# MCU.net
KiCad netlist of a schematic drawn in Altium Designer
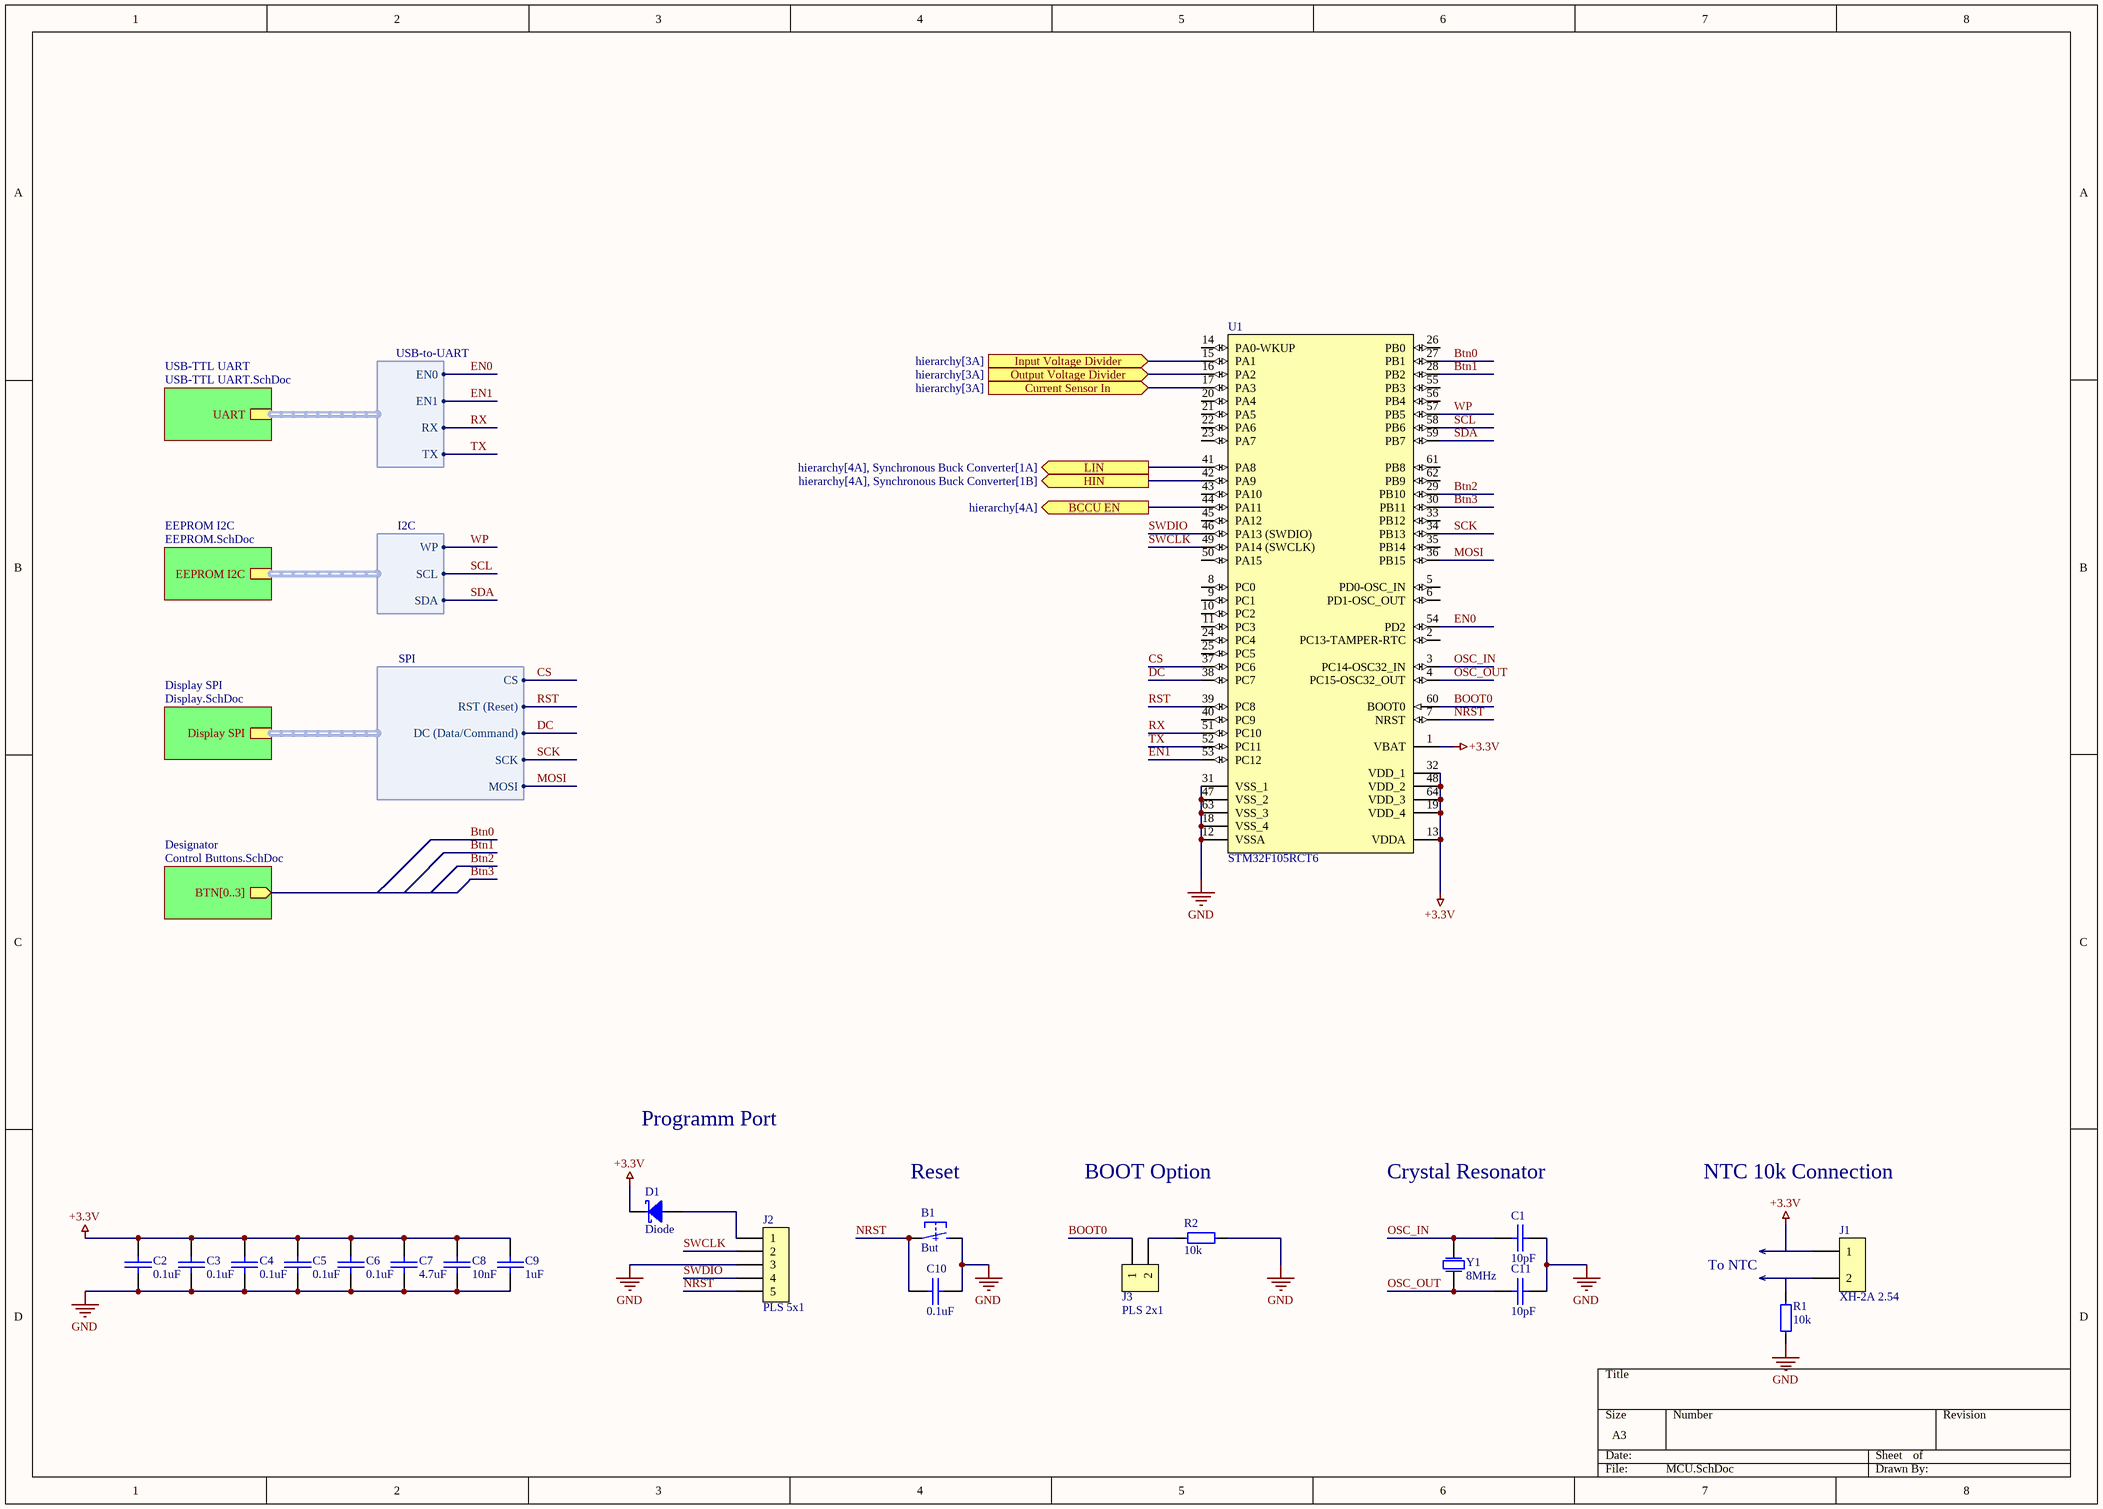
[diagram p0: MCU.SchDoc]

(export (version "E")
  (design (tool "Eeschema 10.0.6"))
  (components
    (comp (ref "B1")
      (value "But")
      (footprint "BUTTON 6x3.5")
      (description "Button 2 Conn SMD")
      (fields
        (field (name "PART NUMBER") "L-KLS7-TS3608-5.0-180")
        (field (name "MANUFACTURER") "KLS electronic co ltd")
      )
      (libsource (lib "BRT_Components") (part "Button 2 Conn"))
    )
    (comp (ref "C1")
      (value "10pF")
      (footprint "0805 Capicator")
      (description "10pF NP0 50V 5% 0805")
      (fields
        (field (name "MANUFACTURER") "Murata Manufacturing")
        (field (name "PART NUMBER") "GRM2165C1H100JZ01D")
      )
      (libsource (lib "BRT_Components") (part "Cap 10pF (0805)"))
    )
    (comp (ref "C2")
      (value "0.1uF")
      (footprint "0603 Capicator")
      (description "0.1uF X7R 16V 10% 0603")
      (fields
        (field (name "MANUFACTURER") "Murata Manufacturing")
        (field (name "PART NUMBER") "GRM188R71C104KA01D")
      )
      (libsource (lib "BRT_Components") (part "Cap 0.1uF (0603)"))
    )
    (comp (ref "C3")
      (value "0.1uF")
      (footprint "0603 Capicator")
      (description "0.1uF X7R 16V 10% 0603")
      (fields
        (field (name "MANUFACTURER") "Murata Manufacturing")
        (field (name "PART NUMBER") "GRM188R71C104KA01D")
      )
      (libsource (lib "BRT_Components") (part "Cap 0.1uF (0603)"))
    )
    (comp (ref "C4")
      (value "0.1uF")
      (footprint "0603 Capicator")
      (description "0.1uF X7R 16V 10% 0603")
      (fields
        (field (name "MANUFACTURER") "Murata Manufacturing")
        (field (name "PART NUMBER") "GRM188R71C104KA01D")
      )
      (libsource (lib "BRT_Components") (part "Cap 0.1uF (0603)"))
    )
    (comp (ref "C5")
      (value "0.1uF")
      (footprint "0603 Capicator")
      (description "0.1uF X7R 16V 10% 0603")
      (fields
        (field (name "MANUFACTURER") "Murata Manufacturing")
        (field (name "PART NUMBER") "GRM188R71C104KA01D")
      )
      (libsource (lib "BRT_Components") (part "Cap 0.1uF (0603)"))
    )
    (comp (ref "C6")
      (value "0.1uF")
      (footprint "0603 Capicator")
      (description "0.1uF X7R 16V 10% 0603")
      (fields
        (field (name "MANUFACTURER") "Murata Manufacturing")
        (field (name "PART NUMBER") "GRM188R71C104KA01D")
      )
      (libsource (lib "BRT_Components") (part "Cap 0.1uF (0603)"))
    )
    (comp (ref "C7")
      (value "4.7uF")
      (footprint "0603 Capicator")
      (description "4.7uF X5R 25V 10% 0603")
      (fields
        (field (name "MANUFACTURER") "Murata Manufacturing")
        (field (name "PART NUMBER") "GRM188R61E475KE11D")
      )
      (libsource (lib "BRT_Components") (part "Cap 4.7uF (0603)"))
    )
    (comp (ref "C8")
      (value "10nF")
      (footprint "0603 Capicator")
      (description "X7R 10nF 100V 10% 0603")
      (fields
        (field (name "MANUFACTURER") "Murata Manufacturing")
        (field (name "PART NUMBER") "GRM188R72A103KA01D")
      )
      (libsource (lib "BRT_Components") (part "Cap 10nF (0603)"))
    )
    (comp (ref "C9")
      (value "1uF")
      (footprint "0603 Capicator")
      (description "1uF X5R 25V 10% 0603")
      (fields
        (field (name "MANUFACTURER") "Murata Manufacturing")
        (field (name "PART NUMBER") "GRM188R61E105KAADD")
      )
      (libsource (lib "BRT_Components") (part "Cap 1uF (0603)"))
    )
    (comp (ref "C10")
      (value "0.1uF")
      (footprint "0805 Capicator")
      (description "0.1uF X7R 25V 10% 0805")
      (fields
        (field (name "MANUFACTURER") "Murata Manufacturing")
        (field (name "PART NUMBER") "GRM21BR71E104KA01L")
      )
      (libsource (lib "BRT_Components") (part "Cap 0.1uF (0805)"))
    )
    (comp (ref "C11")
      (value "10pF")
      (footprint "0805 Capicator")
      (description "10pF NP0 50V 5% 0805")
      (fields
        (field (name "MANUFACTURER") "Murata Manufacturing")
        (field (name "PART NUMBER") "GRM2165C1H100JZ01D")
      )
      (libsource (lib "BRT_Components") (part "Cap 10pF (0805)"))
    )
    (comp (ref "D1")
      (value "Diode")
      (footprint "sod-123")
      (description "0.5 A, Low Forward Voltage less than 385 mV, 400 mW Power Dissipation Package")
      (fields (field (name "PART NUMBER") "MBR0520L") (field (name "MANUFACTURER") "ON Semiconductor"))
      (libsource (lib "BRT_Components") (part "Diode Schottky (SOD-123)"))
    )
    (comp (ref "J1")
      (value "XH-2A 2.54")
      (footprint "CONN 1X2 (XH 2.54)")
      (description "Connector on the board straight 2pin 2.54mm")
      (libsource (lib "Altium_Library") (part "Connector XH-2A 2.54"))
    )
    (comp (ref "J2")
      (value "PLS 5x1")
      (footprint "PLS 5x1")
      (description "Header, 5-Pin")
      (libsource (lib "BRT_Components") (part "Conn 5 (PLS)"))
    )
    (comp (ref "J3")
      (value "PLS 2x1")
      (footprint "PLS 2X1")
      (libsource (lib "BRT_Components") (part "Conn 2 (PLS)"))
    )
    (comp (ref "R1")
      (value "10k")
      (footprint "0805 Resistor")
      (description "0.125W 0805 10k, 1%")
      (fields (field (name "PART NUMBER") "RC0805FR-0710KL") (field (name "MANUFACTURER") "Taiwan"))
      (libsource (lib "BRT_Components") (part "Res 10k (0805)"))
    )
    (comp (ref "R2")
      (value "10k")
      (footprint "0805 Resistor")
      (description "0.125W 0805 10k, 1%")
      (fields (field (name "PART NUMBER") "RC0805FR-0710KL") (field (name "MANUFACTURER") "Taiwan"))
      (libsource (lib "BRT_Components") (part "Res 10k (0805)"))
    )
    (comp (ref "U1")
      (value "STM32F105RCT6")
      (footprint "LQFP64")
      (description "MCU ARM 256KB FLASH MEM 64-LQFP")
      (fields (field (name "MANUFACTURER") "STMicroelectronics"))
      (libsource (lib "BRT_Components") (part "STM32F105RCT6"))
    )
    (comp (ref "Y1")
      (value "8MHz")
      (footprint "R38")
      (description "Crystal. HC-49S (US)")
      (fields (field (name "MANUFACTURER") "China") (field (name "PART NUMBER") "8.000MHzHC-49US"))
      (libsource (lib "BRT_Components") (part "Crystal 8MHz"))
    )
  )
  (nets
    (net (code "4") (name "+3.3V") (class "Default")
      (node (ref "C2") (pin "2") (pinfunction "2_2") (pintype "passive"))
      (node (ref "C3") (pin "2") (pinfunction "2_2") (pintype "passive"))
      (node (ref "C4") (pin "2") (pinfunction "2_2") (pintype "passive"))
      (node (ref "C5") (pin "2") (pinfunction "2_2") (pintype "passive"))
      (node (ref "C6") (pin "2") (pinfunction "2_2") (pintype "passive"))
      (node (ref "C7") (pin "2") (pinfunction "2_2") (pintype "passive"))
      (node (ref "C8") (pin "2") (pinfunction "2_2") (pintype "passive"))
      (node (ref "C9") (pin "2") (pinfunction "2_2") (pintype "passive"))
      (node (ref "D1") (pin "2") (pinfunction "2_2") (pintype "passive"))
      (node (ref "J1") (pin "1") (pinfunction "1_1") (pintype "passive"))
      (node (ref "U1") (pin "1") (pinfunction "VBAT_1") (pintype "power_in"))
      (node (ref "U1") (pin "13") (pinfunction "VDDA_13") (pintype "power_in"))
      (node (ref "U1") (pin "19") (pinfunction "VDD_4_19") (pintype "power_in"))
      (node (ref "U1") (pin "32") (pinfunction "VDD_1_32") (pintype "power_in"))
      (node (ref "U1") (pin "48") (pinfunction "VDD_2_48") (pintype "power_in"))
      (node (ref "U1") (pin "64") (pinfunction "VDD_3_64") (pintype "power_in"))
    )
    (net (code "5") (name "/BCCU EN") (class "Default")
      (node (ref "U1") (pin "44") (pinfunction "PA11_44") (pintype "bidirectional"))
    )
    (net (code "6") (name "/BOOT0") (class "Default")
      (node (ref "J3") (pin "1") (pinfunction "1_1") (pintype "passive"))
      (node (ref "U1") (pin "60") (pinfunction "BOOT0_60") (pintype "input"))
    )
    (net (code "8") (name "/Btn0") (class "Default")
      (node (ref "U1") (pin "27") (pinfunction "PB1_27") (pintype "bidirectional"))
    )
    (net (code "9") (name "/Btn1") (class "Default")
      (node (ref "U1") (pin "28") (pinfunction "PB2_28") (pintype "bidirectional"))
    )
    (net (code "10") (name "/Btn2") (class "Default")
      (node (ref "U1") (pin "29") (pinfunction "PB10_29") (pintype "bidirectional"))
    )
    (net (code "11") (name "/Btn3") (class "Default")
      (node (ref "U1") (pin "30") (pinfunction "PB11_30") (pintype "bidirectional"))
    )
    (net (code "12") (name "/CS") (class "Default")
      (node (ref "U1") (pin "37") (pinfunction "PC6_37") (pintype "bidirectional"))
    )
    (net (code "13") (name "/Current Sensor In") (class "Default")
      (node (ref "U1") (pin "17") (pinfunction "PA3_17") (pintype "bidirectional"))
    )
    (net (code "14") (name "/DC") (class "Default")
      (node (ref "U1") (pin "38") (pinfunction "PC7_38") (pintype "bidirectional"))
    )
    (net (code "15") (name "/EN0") (class "Default")
      (node (ref "U1") (pin "54") (pinfunction "PD2_54") (pintype "bidirectional"))
    )
    (net (code "16") (name "/EN1") (class "Default")
      (node (ref "U1") (pin "53") (pinfunction "PC12_53") (pintype "bidirectional"))
    )
    (net (code "17") (name "/HIN") (class "Default")
      (node (ref "U1") (pin "42") (pinfunction "PA9_42") (pintype "bidirectional"))
    )
    (net (code "18") (name "/Input Voltage Divider") (class "Default")
      (node (ref "U1") (pin "15") (pinfunction "PA1_15") (pintype "bidirectional"))
    )
    (net (code "19") (name "/LIN") (class "Default")
      (node (ref "U1") (pin "41") (pinfunction "PA8_41") (pintype "bidirectional"))
    )
    (net (code "20") (name "/MOSI") (class "Default")
      (node (ref "U1") (pin "36") (pinfunction "PB15_36") (pintype "bidirectional"))
    )
    (net (code "21") (name "/NRST") (class "Default")
      (node (ref "B1") (pin "1") (pinfunction "1_1") (pintype "passive"))
      (node (ref "C10") (pin "1") (pinfunction "1_1") (pintype "passive"))
      (node (ref "J2") (pin "5") (pinfunction "5_5") (pintype "passive"))
      (node (ref "U1") (pin "7") (pinfunction "NRST_7") (pintype "bidirectional"))
    )
    (net (code "22") (name "/OSC_IN") (class "Default")
      (node (ref "C1") (pin "2") (pinfunction "2_2") (pintype "passive"))
      (node (ref "U1") (pin "3") (pinfunction "PC14-OSC32_IN_3") (pintype "bidirectional"))
      (node (ref "Y1") (pin "2") (pinfunction "2_2") (pintype "passive"))
    )
    (net (code "23") (name "/OSC_OUT") (class "Default")
      (node (ref "C11") (pin "2") (pinfunction "2_2") (pintype "passive"))
      (node (ref "U1") (pin "4") (pinfunction "PC15-OSC32_OUT_4") (pintype "bidirectional"))
      (node (ref "Y1") (pin "1") (pinfunction "1_1") (pintype "passive"))
    )
    (net (code "24") (name "/Output Voltage Divider") (class "Default")
      (node (ref "U1") (pin "16") (pinfunction "PA2_16") (pintype "bidirectional"))
    )
    (net (code "25") (name "/RST") (class "Default")
      (node (ref "U1") (pin "39") (pinfunction "PC8_39") (pintype "bidirectional"))
    )
    (net (code "26") (name "/RX") (class "Default")
      (node (ref "U1") (pin "51") (pinfunction "PC10_51") (pintype "bidirectional"))
    )
    (net (code "27") (name "/SCK") (class "Default")
      (node (ref "U1") (pin "34") (pinfunction "PB13_34") (pintype "bidirectional"))
    )
    (net (code "28") (name "/SCL") (class "Default")
      (node (ref "U1") (pin "58") (pinfunction "PB6_58") (pintype "bidirectional"))
    )
    (net (code "29") (name "/SDA") (class "Default")
      (node (ref "U1") (pin "59") (pinfunction "PB7_59") (pintype "bidirectional"))
    )
    (net (code "30") (name "/SWCLK") (class "Default")
      (node (ref "J2") (pin "2") (pinfunction "2_2") (pintype "passive"))
      (node (ref "U1") (pin "49") (pinfunction "PA14_(SWCLK)_49") (pintype "bidirectional"))
    )
    (net (code "31") (name "/SWDIO") (class "Default")
      (node (ref "J2") (pin "4") (pinfunction "4_4") (pintype "passive"))
      (node (ref "U1") (pin "46") (pinfunction "PA13_(SWDIO)_46") (pintype "bidirectional"))
    )
    (net (code "32") (name "/TX") (class "Default")
      (node (ref "U1") (pin "52") (pinfunction "PC11_52") (pintype "bidirectional"))
    )
    (net (code "33") (name "/WP") (class "Default")
      (node (ref "U1") (pin "57") (pinfunction "PB5_57") (pintype "bidirectional"))
    )
    (net (code "37") (name "GND") (class "Default")
      (node (ref "B1") (pin "2") (pinfunction "2_2") (pintype "passive"))
      (node (ref "C1") (pin "1") (pinfunction "1_1") (pintype "passive"))
      (node (ref "C10") (pin "2") (pinfunction "2_2") (pintype "passive"))
      (node (ref "C11") (pin "1") (pinfunction "1_1") (pintype "passive"))
      (node (ref "C2") (pin "1") (pinfunction "1_1") (pintype "passive"))
      (node (ref "C3") (pin "1") (pinfunction "1_1") (pintype "passive"))
      (node (ref "C4") (pin "1") (pinfunction "1_1") (pintype "passive"))
      (node (ref "C5") (pin "1") (pinfunction "1_1") (pintype "passive"))
      (node (ref "C6") (pin "1") (pinfunction "1_1") (pintype "passive"))
      (node (ref "C7") (pin "1") (pinfunction "1_1") (pintype "passive"))
      (node (ref "C8") (pin "1") (pinfunction "1_1") (pintype "passive"))
      (node (ref "C9") (pin "1") (pinfunction "1_1") (pintype "passive"))
      (node (ref "J2") (pin "3") (pinfunction "3_3") (pintype "passive"))
      (node (ref "R1") (pin "1") (pinfunction "1_1") (pintype "passive"))
      (node (ref "R2") (pin "2") (pinfunction "2_2") (pintype "passive"))
      (node (ref "U1") (pin "12") (pinfunction "VSSA_12") (pintype "power_in"))
      (node (ref "U1") (pin "18") (pinfunction "VSS_4_18") (pintype "power_in"))
      (node (ref "U1") (pin "31") (pinfunction "VSS_1_31") (pintype "power_in"))
      (node (ref "U1") (pin "47") (pinfunction "VSS_2_47") (pintype "power_in"))
      (node (ref "U1") (pin "63") (pinfunction "VSS_3_63") (pintype "power_in"))
    )
    (net (code "38") (name "Net-(D1-Pad1)") (class "Default")
      (node (ref "D1") (pin "1") (pinfunction "1_1") (pintype "passive"))
      (node (ref "J2") (pin "1") (pinfunction "1_1") (pintype "passive"))
    )
    (net (code "39") (name "Net-(J1-Pad2)") (class "Default")
      (node (ref "J1") (pin "2") (pinfunction "2_2") (pintype "passive"))
      (node (ref "R1") (pin "2") (pinfunction "2_2") (pintype "passive"))
    )
    (net (code "40") (name "Net-(J3-Pad2)") (class "Default")
      (node (ref "J3") (pin "2") (pinfunction "2_2") (pintype "passive"))
      (node (ref "R2") (pin "1") (pinfunction "1_1") (pintype "passive"))
    )
    (net (code "41") (name "unconnected-(U1-PA0-WKUP-Pad14)") (class "Default")
      (node (ref "U1") (pin "14") (pinfunction "PA0-WKUP_14") (pintype "bidirectional"))
    )
    (net (code "42") (name "unconnected-(U1-PA4-Pad20)") (class "Default")
      (node (ref "U1") (pin "20") (pinfunction "PA4_20") (pintype "bidirectional"))
    )
    (net (code "43") (name "unconnected-(U1-PA5-Pad21)") (class "Default")
      (node (ref "U1") (pin "21") (pinfunction "PA5_21") (pintype "bidirectional"))
    )
    (net (code "44") (name "unconnected-(U1-PA6-Pad22)") (class "Default")
      (node (ref "U1") (pin "22") (pinfunction "PA6_22") (pintype "bidirectional"))
    )
    (net (code "45") (name "unconnected-(U1-PA7-Pad23)") (class "Default")
      (node (ref "U1") (pin "23") (pinfunction "PA7_23") (pintype "bidirectional"))
    )
    (net (code "46") (name "unconnected-(U1-PA10-Pad43)") (class "Default")
      (node (ref "U1") (pin "43") (pinfunction "PA10_43") (pintype "bidirectional"))
    )
    (net (code "47") (name "unconnected-(U1-PA12-Pad45)") (class "Default")
      (node (ref "U1") (pin "45") (pinfunction "PA12_45") (pintype "bidirectional"))
    )
    (net (code "48") (name "unconnected-(U1-PA15-Pad50)") (class "Default")
      (node (ref "U1") (pin "50") (pinfunction "PA15_50") (pintype "bidirectional"))
    )
    (net (code "49") (name "unconnected-(U1-PB0-Pad26)") (class "Default")
      (node (ref "U1") (pin "26") (pinfunction "PB0_26") (pintype "bidirectional"))
    )
    (net (code "50") (name "unconnected-(U1-PB3-Pad55)") (class "Default")
      (node (ref "U1") (pin "55") (pinfunction "PB3_55") (pintype "bidirectional"))
    )
    (net (code "51") (name "unconnected-(U1-PB4-Pad56)") (class "Default")
      (node (ref "U1") (pin "56") (pinfunction "PB4_56") (pintype "bidirectional"))
    )
    (net (code "52") (name "unconnected-(U1-PB8-Pad61)") (class "Default")
      (node (ref "U1") (pin "61") (pinfunction "PB8_61") (pintype "bidirectional"))
    )
    (net (code "53") (name "unconnected-(U1-PB9-Pad62)") (class "Default")
      (node (ref "U1") (pin "62") (pinfunction "PB9_62") (pintype "bidirectional"))
    )
    (net (code "54") (name "unconnected-(U1-PB12-Pad33)") (class "Default")
      (node (ref "U1") (pin "33") (pinfunction "PB12_33") (pintype "bidirectional"))
    )
    (net (code "55") (name "unconnected-(U1-PB14-Pad35)") (class "Default")
      (node (ref "U1") (pin "35") (pinfunction "PB14_35") (pintype "bidirectional"))
    )
    (net (code "56") (name "unconnected-(U1-PC0-Pad8)") (class "Default")
      (node (ref "U1") (pin "8") (pinfunction "PC0_8") (pintype "bidirectional"))
    )
    (net (code "57") (name "unconnected-(U1-PC1-Pad9)") (class "Default")
      (node (ref "U1") (pin "9") (pinfunction "PC1_9") (pintype "bidirectional"))
    )
    (net (code "58") (name "unconnected-(U1-PC2-Pad10)") (class "Default")
      (node (ref "U1") (pin "10") (pinfunction "PC2_10") (pintype "bidirectional"))
    )
    (net (code "59") (name "unconnected-(U1-PC3-Pad11)") (class "Default")
      (node (ref "U1") (pin "11") (pinfunction "PC3_11") (pintype "bidirectional"))
    )
    (net (code "60") (name "unconnected-(U1-PC4-Pad24)") (class "Default")
      (node (ref "U1") (pin "24") (pinfunction "PC4_24") (pintype "bidirectional"))
    )
    (net (code "61") (name "unconnected-(U1-PC5-Pad25)") (class "Default")
      (node (ref "U1") (pin "25") (pinfunction "PC5_25") (pintype "bidirectional"))
    )
    (net (code "62") (name "unconnected-(U1-PC9-Pad40)") (class "Default")
      (node (ref "U1") (pin "40") (pinfunction "PC9_40") (pintype "bidirectional"))
    )
    (net (code "63") (name "unconnected-(U1-PC13-TAMPER-RTC-Pad2)") (class "Default")
      (node (ref "U1") (pin "2") (pinfunction "PC13-TAMPER-RTC_2") (pintype "bidirectional"))
    )
    (net (code "64") (name "unconnected-(U1-PD0-OSC_IN-Pad5)") (class "Default")
      (node (ref "U1") (pin "5") (pinfunction "PD0-OSC_IN_5") (pintype "bidirectional"))
    )
    (net (code "65") (name "unconnected-(U1-PD1-OSC_OUT-Pad6)") (class "Default")
      (node (ref "U1") (pin "6") (pinfunction "PD1-OSC_OUT_6") (pintype "bidirectional"))
    )
  )
)
